# OCP.net
KiCad netlist of a schematic drawn in Altium Designer
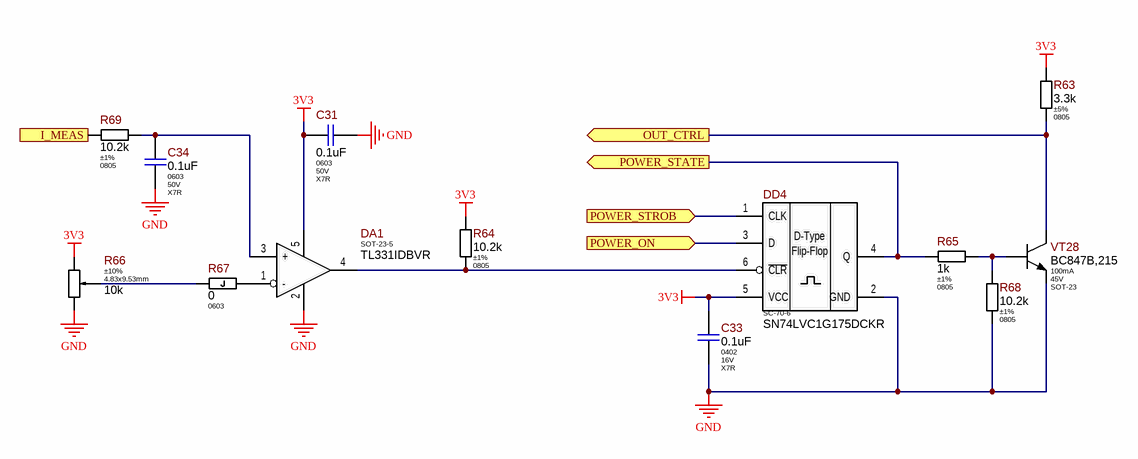
[diagram p0: OCP.SchDoc]

(export (version "E")
  (design (tool "Eeschema 10.0.6"))
  (components
    (comp (ref "C31")
      (value "0.1uF")
      (footprint "C_CERAMIC_0603_MED")
      (description "100nF 50V X7R ±10% 0603 Ceramic Capacitor RoHS")
      (fields
        (field (name "PACKAGE") "0603")
        (field (name "VOLTAGE") "50V")
        (field (name "DIELECTRIC TYPE") "X7R")
        (field (name "PART NUMBER") "CL10B104KB8NNND")
        (field (name "MANUFACTURER") "Samsung Electro-Mechanics")
      )
      (libsource (lib "capacitors") (part "CL10B104KB8NNND"))
    )
    (comp (ref "C33")
      (value "0.1uF")
      (footprint "C_CERAMIC_0402_MED")
      (description "100nF 16V X7R ±10% 0402 Ceramic Capacitor RoHS")
      (fields
        (field (name "PACKAGE") "0402")
        (field (name "VOLTAGE") "16V")
        (field (name "DIELECTRIC TYPE") "X7R")
        (field (name "PART NUMBER") "CC0402KPX7R7BB104")
        (field (name "MANUFACTURER") "Yageo")
      )
      (libsource (lib "AjaxLibrary") (part "Capacitor-NonPolar"))
    )
    (comp (ref "C34")
      (value "0.1uF")
      (footprint "C_CERAMIC_0603_MED")
      (description "100nF 50V X7R ±10% 0603 Ceramic Capacitor RoHS")
      (fields
        (field (name "PACKAGE") "0603")
        (field (name "VOLTAGE") "50V")
        (field (name "DIELECTRIC TYPE") "X7R")
        (field (name "PART NUMBER") "CL10B104KB8NNND")
        (field (name "MANUFACTURER") "Samsung Electro-Mechanics")
      )
      (libsource (lib "capacitors") (part "CL10B104KB8NNND"))
    )
    (comp (ref "DA1")
      (value "TL331IDBVR")
      (footprint "SOT-23-5")
      (description "Up to 36V, Single Comparator, Open Collector Output, 700uA Supply Current, SOT-23-5")
      (fields
        (field (name "PACKAGE") "SOT-23-5")
        (field (name "PART NUMBER") "TL331IDBVR")
        (field (name "MANUFACTURER") "Texas Instruments")
      )
      (libsource (lib "ic") (part "TL331IDBVR"))
    )
    (comp (ref "DD4")
      (value "SN74LVC1G175DCKR")
      (footprint "SC-70-6")
      (description "Single D-type Flip-Flop with Asynchronous Clear, Positive Edge Trigger, SC-70-6")
      (fields
        (field (name "PACKAGE") "SC-70-6")
        (field (name "PART NUMBER") "SN74LVC1G175DCKR")
        (field (name "MANUFACTURER") "Texas Instruments")
      )
      (libsource (lib "AjaxLibrary") (part "SN74LVC1G175DCKR"))
    )
    (comp (ref "R63")
      (value "3.3k")
      (footprint "R_ANY_CHIP_0805_MED")
      (description "3.3 kOhms ±5%, 1/8W 0805 Thick Film Resistor")
      (fields
        (field (name "TOLERANCE") "±5%")
        (field (name "PACKAGE") "0805")
        (field (name "PART NUMBER") "RC0805JR-073K3L")
        (field (name "MANUFACTURER") "Yageo")
      )
      (libsource (lib "resistors") (part "RC0805JR-073K3L"))
    )
    (comp (ref "R64")
      (value "10.2k")
      (footprint "R_ANY_CHIP_0805_MED")
      (description "10.2 kOhms ±1%, 1/8W 0805 Thick Film Resistor")
      (fields
        (field (name "TOLERANCE") "±1%")
        (field (name "PACKAGE") "0805")
        (field (name "PART NUMBER") "RC0805FR-0710K2L")
        (field (name "MANUFACTURER") "Yageo")
      )
      (libsource (lib "resistors") (part "RC0805FR-0710K2L"))
    )
    (comp (ref "R65")
      (value "1k")
      (footprint "R_ANY_CHIP_0805_MED")
      (description "1 kOhms ±1%, 1/8W 0805 Thick Film Resistor")
      (fields
        (field (name "TOLERANCE") "±1%")
        (field (name "PACKAGE") "0805")
        (field (name "PART NUMBER") "RC0805FR-0710K2L")
        (field (name "MANUFACTURER") "Yageo")
      )
      (libsource (lib "resistors") (part "RC0805FR-0710K2L"))
    )
    (comp (ref "R66")
      (value "10k")
      (footprint "3296W-1-xxx")
      (description "10 kOhms ±10% Trimmer Resistor, 0.5W, Through Hole 3/8\", 4.83x9.53mm, 10.03mm Height")
      (fields
        (field (name "TOLERANCE") "±10%")
        (field (name "PACKAGE") "4.83x9.53mm")
        (field (name "PART NUMBER") "3296W-1-103LF")
        (field (name "MANUFACTURER") "Bourns")
      )
      (libsource (lib "resistors") (part "3296W-1-103LF"))
    )
    (comp (ref "R67")
      (value "0")
      (footprint "R_ANY_CHIP_0603_MED")
      (description "0 Ohms Jumper, 1/10W 0603 Thick Film Resistor")
      (fields
        (field (name "TOLERANCE") "±5%")
        (field (name "PACKAGE") "0603")
        (field (name "PART NUMBER") "RC0603JR-070RL")
      )
      (libsource (lib "resistors") (part "RC0603JR-070RL"))
    )
    (comp (ref "R68")
      (value "10.2k")
      (footprint "R_ANY_CHIP_0805_MED")
      (description "10.2 kOhms ±1%, 1/8W 0805 Thick Film Resistor")
      (fields
        (field (name "TOLERANCE") "±1%")
        (field (name "PACKAGE") "0805")
        (field (name "PART NUMBER") "RC0805FR-0710K2L")
        (field (name "MANUFACTURER") "Yageo")
      )
      (libsource (lib "resistors") (part "RC0805FR-0710K2L"))
    )
    (comp (ref "R69")
      (value "10.2k")
      (footprint "R_ANY_CHIP_0805_MED")
      (description "10.2 kOhms ±1%, 1/8W 0805 Thick Film Resistor")
      (fields
        (field (name "TOLERANCE") "±1%")
        (field (name "PACKAGE") "0805")
        (field (name "PART NUMBER") "RC0805FR-0710K2L")
        (field (name "MANUFACTURER") "Yageo")
      )
      (libsource (lib "resistors") (part "RC0805FR-0710K2L"))
    )
    (comp (ref "VT28")
      (value "BC847B")
      (footprint "SOT-23_MED")
      (description "45V, 100mA NPN General Purpose Transistor")
      (fields
        (field (name "PART NUMBER") "BC847B,215")
        (field (name "IC") "100mA")
        (field (name "VCE") "45V")
        (field (name "PACKAGE") "SOT-23")
        (field (name "MANUFACTURER") "Nexperia USA")
      )
      (libsource (lib "AjaxLibrary") (part "Bipolar-NPN"))
    )
  )
  (nets
    (net (code "1") (name "/I_MEAS") (class "Default") (node (ref "R69") (pin "2") (pintype "passive")))
    (net (code "2") (name "/OUT_CTRL") (class "Default")
      (node (ref "R63") (pin "2") (pintype "passive"))
      (node (ref "VT28") (pin "3") (pinfunction "C_3") (pintype "passive"))
    )
    (net (code "3") (name "/POWER_ON") (class "Default")
      (node (ref "DD4") (pin "3") (pinfunction "D_3") (pintype "passive"))
    )
    (net (code "4") (name "/POWER_STATE") (class "Default")
      (node (ref "DD4") (pin "4") (pinfunction "Q_4") (pintype "passive"))
      (node (ref "R65") (pin "1") (pintype "passive"))
    )
    (net (code "5") (name "/POWER_STROB") (class "Default")
      (node (ref "DD4") (pin "1") (pinfunction "CLK_1") (pintype "passive"))
    )
    (net (code "6") (name "3V3") (class "Default")
      (node (ref "C31") (pin "2") (pinfunction "2_2") (pintype "passive"))
      (node (ref "C33") (pin "1") (pinfunction "1_1") (pintype "passive"))
      (node (ref "DA1") (pin "5") (pinfunction "VCC_5") (pintype "passive"))
      (node (ref "DD4") (pin "5") (pinfunction "VCC_5") (pintype "passive"))
      (node (ref "R63") (pin "1") (pintype "passive"))
      (node (ref "R64") (pin "2") (pintype "passive"))
      (node (ref "R66") (pin "1") (pinfunction "CCW_1") (pintype "passive"))
    )
    (net (code "7") (name "GND") (class "Default")
      (node (ref "C31") (pin "1") (pinfunction "1_1") (pintype "passive"))
      (node (ref "C33") (pin "2") (pinfunction "2_2") (pintype "passive"))
      (node (ref "C34") (pin "2") (pinfunction "2_2") (pintype "passive"))
      (node (ref "DA1") (pin "2") (pinfunction "GND_2") (pintype "passive"))
      (node (ref "DD4") (pin "2") (pinfunction "GND_2") (pintype "passive"))
      (node (ref "R66") (pin "3") (pinfunction "CW_3") (pintype "passive"))
      (node (ref "R68") (pin "1") (pintype "passive"))
      (node (ref "VT28") (pin "2") (pinfunction "E_2") (pintype "passive"))
    )
    (net (code "8") (name "Net-(DA1-+)") (class "Default")
      (node (ref "C34") (pin "1") (pinfunction "1_1") (pintype "passive"))
      (node (ref "DA1") (pin "3") (pinfunction "+_3") (pintype "passive"))
      (node (ref "R69") (pin "1") (pintype "passive"))
    )
    (net (code "9") (name "Net-(DA1--)") (class "Default")
      (node (ref "DA1") (pin "1") (pinfunction "-_1") (pintype "passive"))
      (node (ref "R67") (pin "1") (pintype "passive"))
    )
    (net (code "10") (name "Net-(DA1-OUT)") (class "Default")
      (node (ref "DA1") (pin "4") (pinfunction "OUT_4") (pintype "passive"))
      (node (ref "DD4") (pin "6") (pinfunction "~{CLR}_6") (pintype "passive"))
      (node (ref "R64") (pin "1") (pintype "passive"))
    )
    (net (code "11") (name "Net-(R66-WIPER)") (class "Default")
      (node (ref "R66") (pin "2") (pinfunction "WIPER_2") (pintype "passive"))
      (node (ref "R67") (pin "2") (pintype "passive"))
    )
    (net (code "12") (name "Net-(VT28-B)") (class "Default")
      (node (ref "R65") (pin "2") (pintype "passive"))
      (node (ref "R68") (pin "2") (pintype "passive"))
      (node (ref "VT28") (pin "1") (pinfunction "B_1") (pintype "passive"))
    )
  )
)
